# Clock_Module.net
KiCad netlist of a schematic drawn in EAGLE
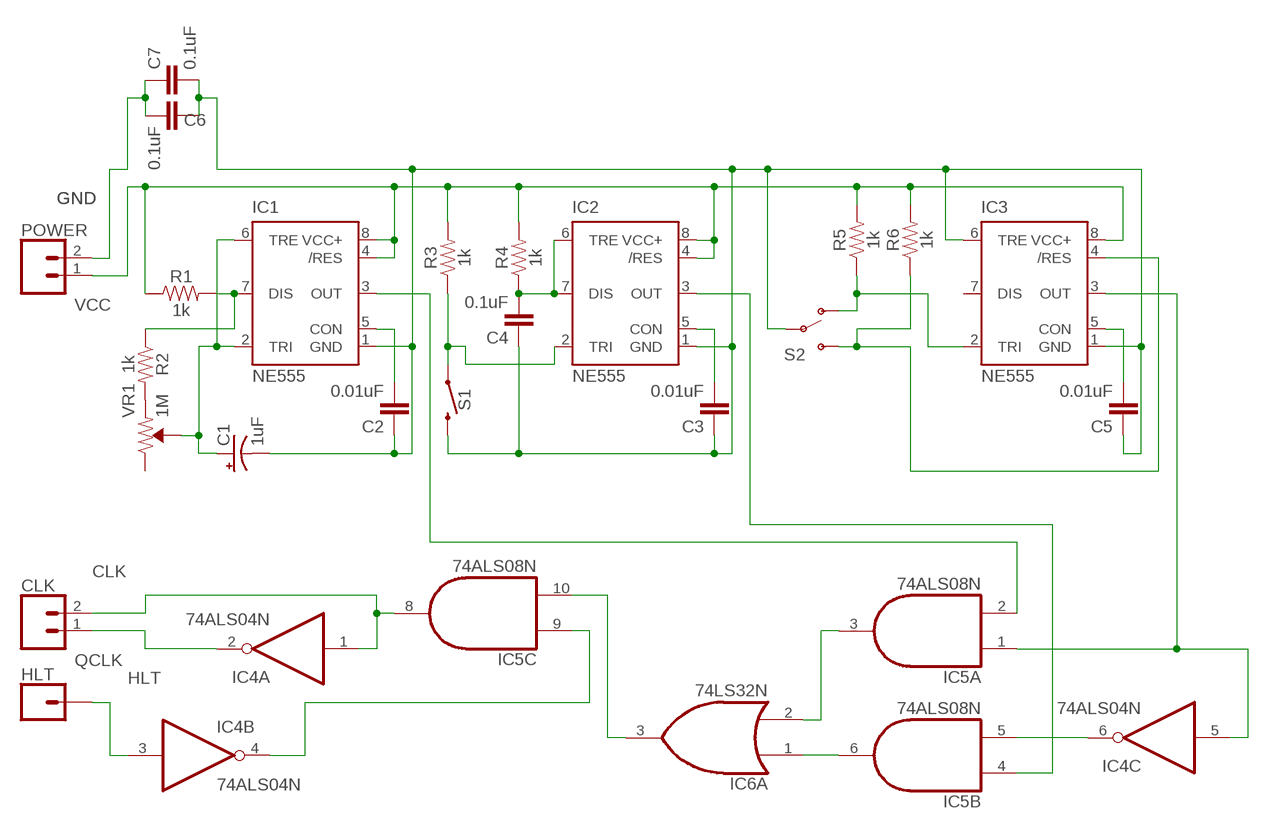
[diagram p0: schematic, sheet 1]

(export (version "E")
  (design (tool "Eeschema 10.0.6"))
  (components
    (comp (ref "C1")
      (value "1uF")
      (footprint "eagle-import:CPOL-RADIAL-2.5MM-6.5MM")
      (libsource (lib "eagle-import") (part "100UF-POLAR-RADIAL-2.5MM-25V-20%"))
    )
    (comp (ref "C2")
      (value "0.01uF")
      (footprint "eagle-import:0603")
      (libsource (lib "eagle-import") (part "0.1UF-0603-100V-10%"))
    )
    (comp (ref "C3")
      (value "0.01uF")
      (footprint "eagle-import:0603")
      (libsource (lib "eagle-import") (part "0.1UF-0603-100V-10%"))
    )
    (comp (ref "C4")
      (value "0.1uF")
      (footprint "eagle-import:0603")
      (libsource (lib "eagle-import") (part "0.1UF-0603-100V-10%"))
    )
    (comp (ref "C5")
      (value "0.01uF")
      (footprint "eagle-import:0603")
      (libsource (lib "eagle-import") (part "0.1UF-0603-100V-10%"))
    )
    (comp (ref "C6")
      (value "0.1uF")
      (footprint "eagle-import:0603")
      (libsource (lib "eagle-import") (part "0.1UF-0603-100V-10%"))
    )
    (comp (ref "C7")
      (value "0.1uF")
      (footprint "eagle-import:0603")
      (libsource (lib "eagle-import") (part "0.1UF-0603-100V-10%"))
    )
    (comp (ref "CLK")
      (value "CONN_02POGO_PIN_HOLES_ONLY")
      (footprint "eagle-import:1X02_PP_HOLES_ONLY")
      (libsource (lib "eagle-import") (part "CONN_02POGO_PIN_HOLES_ONLY"))
    )
    (comp (ref "HLT")
      (value "CONN_01")
      (footprint "eagle-import:1X01")
      (libsource (lib "eagle-import") (part "CONN_01"))
    )
    (comp (ref "IC1")
      (value "NE555")
      (footprint "eagle-import:DIL-08")
      (fields (field (name "MF") "Arrow Electronics") (field (name "MPN") "NE555N"))
      (libsource (lib "eagle-import") (part "NE555"))
    )
    (comp (ref "IC2")
      (value "NE555")
      (footprint "eagle-import:DIL-08")
      (fields (field (name "MF") "Arrow Electronics") (field (name "MPN") "NE555N"))
      (libsource (lib "eagle-import") (part "NE555"))
    )
    (comp (ref "IC3")
      (value "NE555")
      (footprint "eagle-import:DIL-08")
      (fields (field (name "MF") "Arrow Electronics") (field (name "MPN") "NE555N"))
      (libsource (lib "eagle-import") (part "NE555"))
    )
    (comp (ref "IC4")
      (value "74ALS04N")
      (footprint "eagle-import:DIL14")
      (libsource (lib "eagle-import") (part "7404NALS"))
    )
    (comp (ref "IC5")
      (value "74ALS08N")
      (footprint "eagle-import:DIL14")
      (libsource (lib "eagle-import") (part "7408NALS"))
    )
    (comp (ref "IC6")
      (value "74LS32N")
      (footprint "eagle-import:DIL14")
      (libsource (lib "eagle-import") (part "7432NLS"))
    )
    (comp (ref "POWER")
      (value "CONN_02POGO_PIN_HOLES_ONLY")
      (footprint "eagle-import:1X02_PP_HOLES_ONLY")
      (libsource (lib "eagle-import") (part "CONN_02POGO_PIN_HOLES_ONLY"))
    )
    (comp (ref "R1")
      (value "1k")
      (footprint "eagle-import:AXIAL-0.3")
      (libsource (lib "eagle-import") (part "1KOHM-HORIZ-1/4W-5%"))
    )
    (comp (ref "R2")
      (value "1k")
      (footprint "eagle-import:AXIAL-0.3")
      (libsource (lib "eagle-import") (part "1KOHM-HORIZ-1/4W-5%"))
    )
    (comp (ref "R3")
      (value "1k")
      (footprint "eagle-import:AXIAL-0.3")
      (libsource (lib "eagle-import") (part "1KOHM-HORIZ-1/4W-5%"))
    )
    (comp (ref "R4")
      (value "1k")
      (footprint "eagle-import:AXIAL-0.3")
      (libsource (lib "eagle-import") (part "1KOHM-HORIZ-1/4W-5%"))
    )
    (comp (ref "R5")
      (value "1k")
      (footprint "eagle-import:AXIAL-0.3")
      (libsource (lib "eagle-import") (part "1KOHM-HORIZ-1/4W-5%"))
    )
    (comp (ref "R6")
      (value "1k")
      (footprint "eagle-import:AXIAL-0.3")
      (libsource (lib "eagle-import") (part "1KOHM-HORIZ-1/4W-5%"))
    )
    (comp (ref "S1")
      (value "MOMENTARY-SWITCH-SPST-PTH-12MM")
      (footprint "eagle-import:TACTILE_SWITCH_PTH_12MM")
      (libsource (lib "eagle-import") (part "MOMENTARY-SWITCH-SPST-PTH-12MM"))
    )
    (comp (ref "S2")
      (value "SWITCH-SPDT-PTH-11.6X4.0MM")
      (footprint "eagle-import:SWITCH_SPDT_PTH_11.6X4.0MM")
      (libsource (lib "eagle-import") (part "SWITCH-SPDT-PTH-11.6X4.0MM"))
    )
    (comp (ref "VR1")
      (value "1M")
      (footprint "eagle-import:TRIMPOT-PTH-3386U")
      (libsource (lib "eagle-import") (part "TRIMPOT-PTH-10MM-KNOB-1/2W-10%"))
    )
  )
  (nets
    (net (code "1") (name "/CLK") (class "Default")
      (node (ref "CLK") (pin "2") (pinfunction "2_2") (pintype "passive"))
      (node (ref "IC4") (pin "1") (pinfunction "I_1") (pintype "input"))
      (node (ref "IC5") (pin "8") (pinfunction "O_8") (pintype "output"))
    )
    (net (code "2") (name "/GND") (class "Default")
      (node (ref "C6") (pin "2") (pinfunction "2_2") (pintype "passive"))
      (node (ref "C7") (pin "1") (pinfunction "1_1") (pintype "passive"))
      (node (ref "POWER") (pin "2") (pinfunction "2_2") (pintype "passive"))
    )
    (net (code "3") (name "/HLT") (class "Default")
      (node (ref "HLT") (pin "1") (pinfunction "1_1") (pintype "passive"))
      (node (ref "IC4") (pin "3") (pinfunction "I_3") (pintype "input"))
    )
    (net (code "4") (name "/QCLK") (class "Default")
      (node (ref "CLK") (pin "1") (pinfunction "1_1") (pintype "passive"))
      (node (ref "IC4") (pin "2") (pinfunction "O_2") (pintype "output"))
    )
    (net (code "5") (name "/VCC") (class "Default")
      (node (ref "IC1") (pin "4") (pinfunction "/RES_4") (pintype "input"))
      (node (ref "IC1") (pin "8") (pinfunction "VCC+_8") (pintype "power_in"))
      (node (ref "IC2") (pin "4") (pinfunction "/RES_4") (pintype "input"))
      (node (ref "IC2") (pin "8") (pinfunction "VCC+_8") (pintype "power_in"))
      (node (ref "IC3") (pin "8") (pinfunction "VCC+_8") (pintype "power_in"))
      (node (ref "POWER") (pin "1") (pinfunction "1_1") (pintype "passive"))
      (node (ref "R1") (pin "P$1") (pinfunction "1_P$1") (pintype "passive"))
      (node (ref "R3") (pin "P$2") (pinfunction "2_P$2") (pintype "passive"))
      (node (ref "R4") (pin "P$2") (pinfunction "2_P$2") (pintype "passive"))
      (node (ref "R5") (pin "P$2") (pinfunction "2_P$2") (pintype "passive"))
      (node (ref "R6") (pin "P$2") (pinfunction "2_P$2") (pintype "passive"))
    )
    (net (code "6") (name "Net-(C1-+)") (class "Default")
      (node (ref "C1") (pin "1") (pinfunction "+_1") (pintype "passive"))
      (node (ref "IC1") (pin "2") (pinfunction "TRI_2") (pintype "input"))
      (node (ref "IC1") (pin "6") (pinfunction "TRE_6") (pintype "input"))
      (node (ref "VR1") (pin "2") (pinfunction "WIPER_2") (pintype "passive"))
    )
    (net (code "7") (name "Net-(C1--)") (class "Default")
      (node (ref "C1") (pin "2") (pinfunction "-_2") (pintype "passive"))
      (node (ref "C2") (pin "1") (pinfunction "1_1") (pintype "passive"))
      (node (ref "C3") (pin "1") (pinfunction "1_1") (pintype "passive"))
      (node (ref "C4") (pin "1") (pinfunction "1_1") (pintype "passive"))
      (node (ref "C5") (pin "1") (pinfunction "1_1") (pintype "passive"))
      (node (ref "C6") (pin "1") (pinfunction "1_1") (pintype "passive"))
      (node (ref "C7") (pin "2") (pinfunction "2_2") (pintype "passive"))
      (node (ref "IC1") (pin "1") (pinfunction "GND_1") (pintype "power_in"))
      (node (ref "IC2") (pin "1") (pinfunction "GND_1") (pintype "power_in"))
      (node (ref "IC3") (pin "1") (pinfunction "GND_1") (pintype "power_in"))
      (node (ref "IC3") (pin "6") (pinfunction "TRE_6") (pintype "input"))
      (node (ref "S1") (pin "3") (pinfunction "2_3") (pintype "passive"))
      (node (ref "S2") (pin "2") (pinfunction "P_2") (pintype "passive"))
    )
    (net (code "8") (name "Net-(IC1-CON)") (class "Default")
      (node (ref "C2") (pin "2") (pinfunction "2_2") (pintype "passive"))
      (node (ref "IC1") (pin "5") (pinfunction "CON_5") (pintype "input"))
    )
    (net (code "9") (name "Net-(IC1-DIS)") (class "Default")
      (node (ref "IC1") (pin "7") (pinfunction "DIS_7") (pintype "input"))
      (node (ref "R1") (pin "P$2") (pinfunction "2_P$2") (pintype "passive"))
      (node (ref "R2") (pin "P$1") (pinfunction "1_P$1") (pintype "passive"))
    )
    (net (code "10") (name "Net-(IC1-OUT)") (class "Default")
      (node (ref "IC1") (pin "3") (pinfunction "OUT_3") (pintype "output"))
      (node (ref "IC5") (pin "2") (pinfunction "I1_2") (pintype "input"))
    )
    (net (code "11") (name "Net-(IC2-CON)") (class "Default")
      (node (ref "C3") (pin "2") (pinfunction "2_2") (pintype "passive"))
      (node (ref "IC2") (pin "5") (pinfunction "CON_5") (pintype "input"))
    )
    (net (code "12") (name "Net-(IC2-DIS)") (class "Default")
      (node (ref "C4") (pin "2") (pinfunction "2_2") (pintype "passive"))
      (node (ref "IC2") (pin "6") (pinfunction "TRE_6") (pintype "input"))
      (node (ref "IC2") (pin "7") (pinfunction "DIS_7") (pintype "input"))
      (node (ref "R4") (pin "P$1") (pinfunction "1_P$1") (pintype "passive"))
    )
    (net (code "13") (name "Net-(IC2-OUT)") (class "Default")
      (node (ref "IC2") (pin "3") (pinfunction "OUT_3") (pintype "output"))
      (node (ref "IC5") (pin "4") (pinfunction "I0_4") (pintype "input"))
    )
    (net (code "14") (name "Net-(IC2-TRI)") (class "Default")
      (node (ref "IC2") (pin "2") (pinfunction "TRI_2") (pintype "input"))
      (node (ref "R3") (pin "P$1") (pinfunction "1_P$1") (pintype "passive"))
      (node (ref "S1") (pin "1") (pinfunction "1_1") (pintype "passive"))
    )
    (net (code "15") (name "Net-(IC3-CON)") (class "Default")
      (node (ref "C5") (pin "2") (pinfunction "2_2") (pintype "passive"))
      (node (ref "IC3") (pin "5") (pinfunction "CON_5") (pintype "input"))
    )
    (net (code "16") (name "Net-(IC3-OUT)") (class "Default")
      (node (ref "IC3") (pin "3") (pinfunction "OUT_3") (pintype "output"))
      (node (ref "IC4") (pin "5") (pinfunction "I_5") (pintype "input"))
      (node (ref "IC5") (pin "1") (pinfunction "I0_1") (pintype "input"))
    )
    (net (code "17") (name "Net-(IC3-TRI)") (class "Default")
      (node (ref "IC3") (pin "2") (pinfunction "TRI_2") (pintype "input"))
      (node (ref "R5") (pin "P$1") (pinfunction "1_P$1") (pintype "passive"))
      (node (ref "S2") (pin "1") (pinfunction "O_1") (pintype "passive"))
    )
    (net (code "18") (name "Net-(IC3-{slash}RES)") (class "Default")
      (node (ref "IC3") (pin "4") (pinfunction "/RES_4") (pintype "input"))
      (node (ref "R6") (pin "P$1") (pinfunction "1_P$1") (pintype "passive"))
      (node (ref "S2") (pin "3") (pinfunction "S_3") (pintype "passive"))
    )
    (net (code "19") (name "Net-(IC4B-O)") (class "Default")
      (node (ref "IC4") (pin "4") (pinfunction "O_4") (pintype "output"))
      (node (ref "IC5") (pin "9") (pinfunction "I0_9") (pintype "input"))
    )
    (net (code "20") (name "Net-(IC4C-O)") (class "Default")
      (node (ref "IC4") (pin "6") (pinfunction "O_6") (pintype "output"))
      (node (ref "IC5") (pin "5") (pinfunction "I1_5") (pintype "input"))
    )
    (net (code "21") (name "Net-(IC5A-O)") (class "Default")
      (node (ref "IC5") (pin "3") (pinfunction "O_3") (pintype "output"))
      (node (ref "IC6") (pin "2") (pinfunction "I1_2") (pintype "input"))
    )
    (net (code "22") (name "Net-(IC5B-O)") (class "Default")
      (node (ref "IC5") (pin "6") (pinfunction "O_6") (pintype "output"))
      (node (ref "IC6") (pin "1") (pinfunction "I0_1") (pintype "input"))
    )
    (net (code "23") (name "Net-(IC5C-I1)") (class "Default")
      (node (ref "IC5") (pin "10") (pinfunction "I1_10") (pintype "input"))
      (node (ref "IC6") (pin "3") (pinfunction "O_3") (pintype "output"))
    )
    (net (code "24") (name "Net-(R2-2)") (class "Default")
      (node (ref "R2") (pin "P$2") (pinfunction "2_P$2") (pintype "passive"))
      (node (ref "VR1") (pin "1") (pinfunction "CCW_1") (pintype "passive"))
    )
    (net (code "25") (name "unconnected-(IC3-DIS-Pad7)") (class "Default")
      (node (ref "IC3") (pin "7") (pinfunction "DIS_7") (pintype "input"))
    )
    (net (code "26") (name "unconnected-(VR1-CW-Pad3)") (class "Default")
      (node (ref "VR1") (pin "3") (pinfunction "CW_3") (pintype "passive"))
    )
  )
)
